# telecommandeV.net
KiCad netlist of a schematic drawn in EAGLE
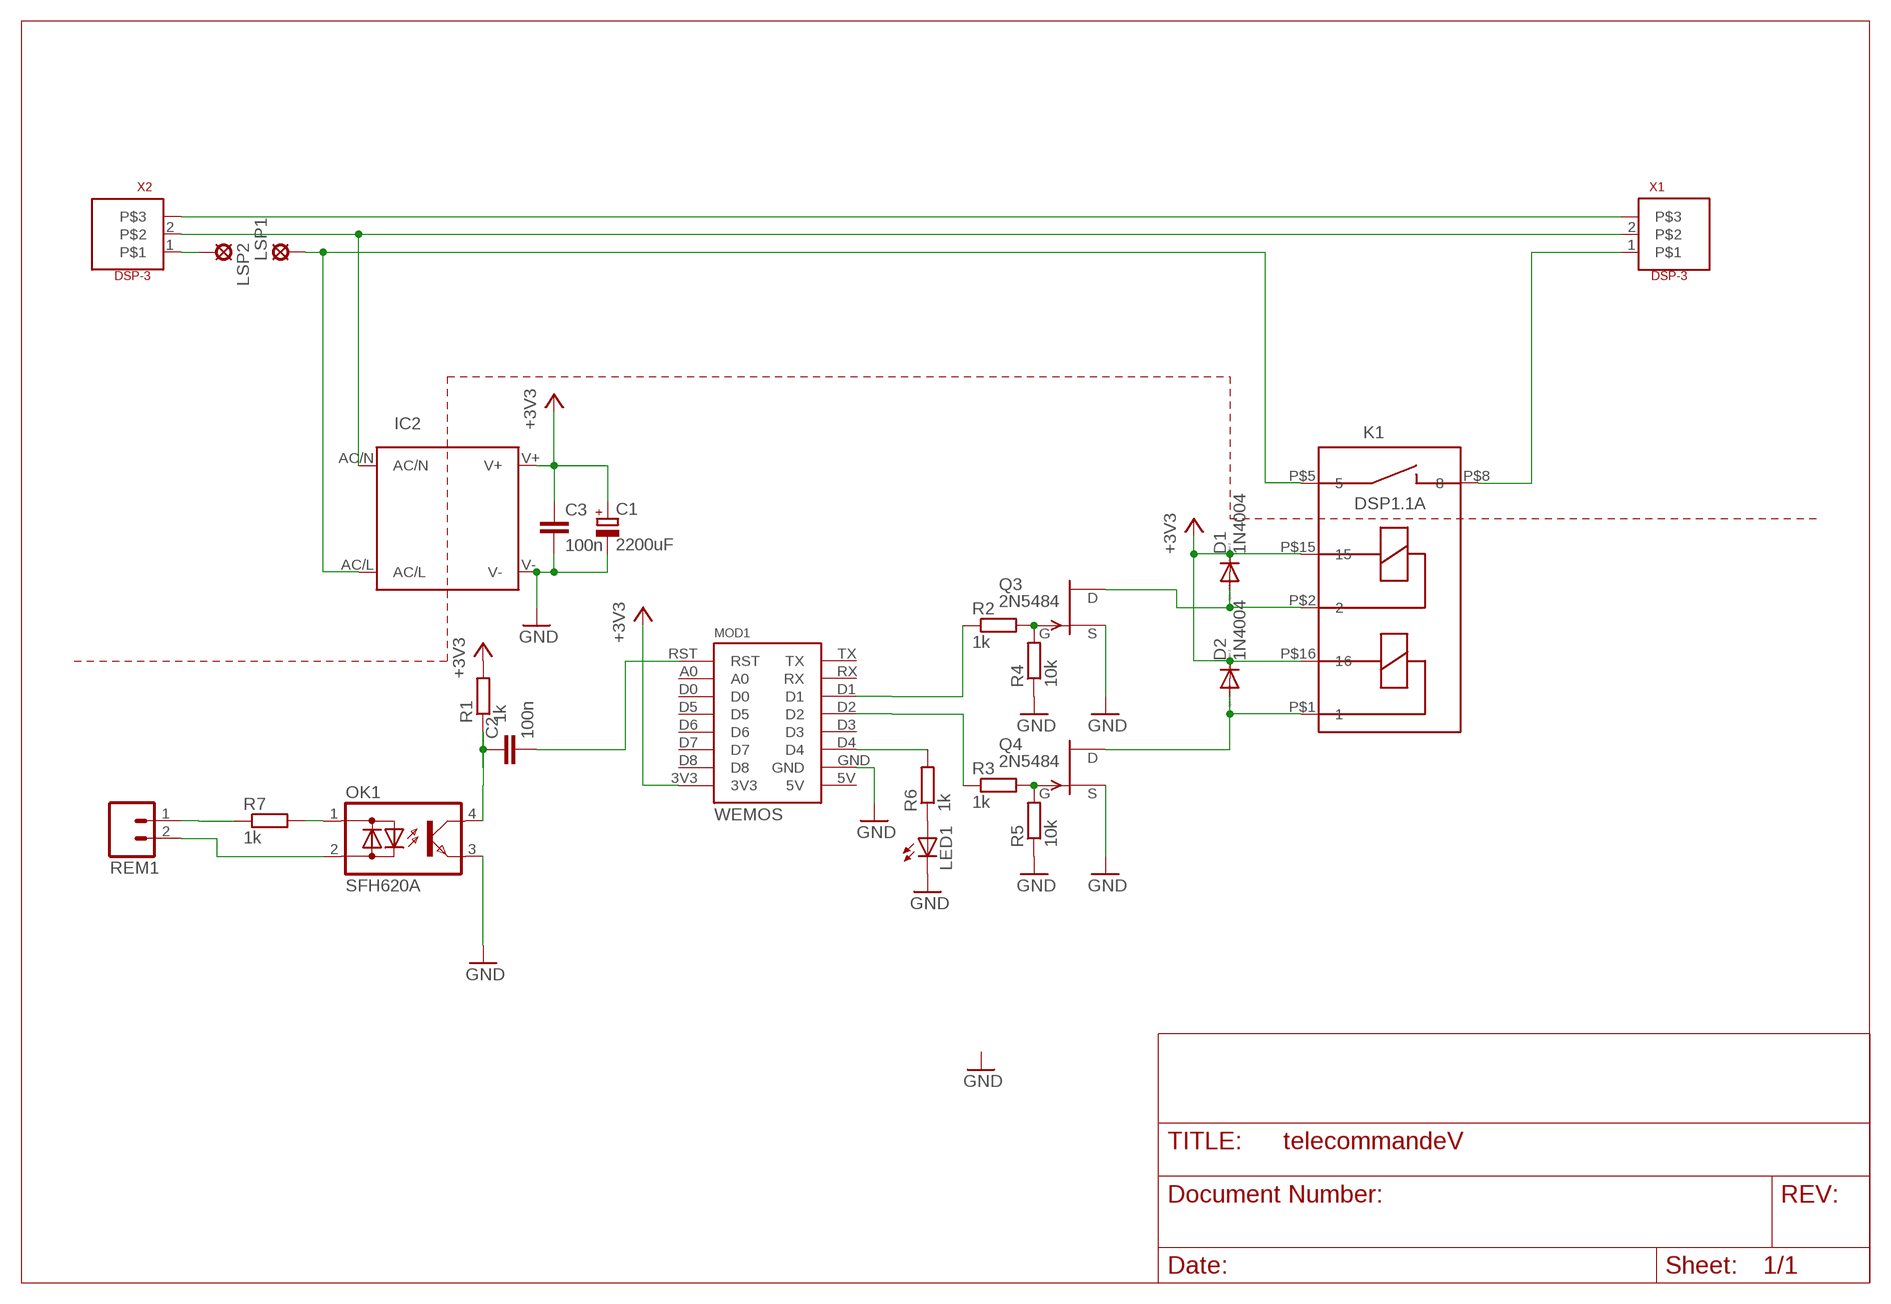
[diagram p0: schematic, sheet 1]

(export (version "E")
  (design (tool "Eeschema 10.0.6"))
  (components
    (comp (ref "C1")
      (value "2200uF")
      (footprint "eagle-import:E3,5-10")
      (libsource (lib "eagle-import") (part "CPOL-EUE3.5-10"))
    )
    (comp (ref "C2")
      (value "100n")
      (footprint "eagle-import:C025-024X044")
      (libsource (lib "eagle-import") (part "C-EU025-024X044"))
    )
    (comp (ref "C3")
      (value "100n")
      (footprint "eagle-import:C025-024X044")
      (libsource (lib "eagle-import") (part "C-EU025-024X044"))
    )
    (comp (ref "D1")
      (value "1N4004")
      (footprint "eagle-import:DO41-10")
      (libsource (lib "eagle-import") (part "1N4004"))
    )
    (comp (ref "D2")
      (value "1N4004")
      (footprint "eagle-import:DO41-10")
      (libsource (lib "eagle-import") (part "1N4004"))
    )
    (comp (ref "IC2")
      (value "IRM_03")
      (footprint "eagle-import:IRM_03")
      (libsource (lib "eagle-import") (part "IRM_03"))
    )
    (comp (ref "K1")
      (value "DSP1.1A")
      (footprint "eagle-import:DSP1A")
      (libsource (lib "eagle-import") (part "DSP1.1A"))
    )
    (comp (ref "LED1")
      (value "LED3MM")
      (footprint "eagle-import:LED3MM")
      (libsource (lib "eagle-import") (part "LED3MM"))
    )
    (comp (ref "LSP1")
      (value "SE14")
      (footprint "eagle-import:SE14")
      (libsource (lib "eagle-import") (part "SE14"))
    )
    (comp (ref "LSP2")
      (value "SE14")
      (footprint "eagle-import:SE14")
      (libsource (lib "eagle-import") (part "SE14"))
    )
    (comp (ref "MOD1")
      (value "WEMOS")
      (footprint "eagle-import:WEMOS")
      (libsource (lib "eagle-import") (part "WEMOS"))
    )
    (comp (ref "OK1")
      (value "SFH620A")
      (footprint "eagle-import:DIL04")
      (fields (field (name "MPN") "SFH620A-2"))
      (libsource (lib "eagle-import") (part "SFH620A"))
    )
    (comp (ref "Q3")
      (value "2N5484")
      (footprint "eagle-import:TO92-")
      (libsource (lib "eagle-import") (part "?5482N4"))
    )
    (comp (ref "Q4")
      (value "2N5484")
      (footprint "eagle-import:TO92-")
      (libsource (lib "eagle-import") (part "?5482N4"))
    )
    (comp (ref "R1")
      (value "1k")
      (footprint "eagle-import:0204_7")
      (libsource (lib "eagle-import") (part "R-EU_0204/7"))
    )
    (comp (ref "R2")
      (value "1k")
      (footprint "eagle-import:0204_7")
      (libsource (lib "eagle-import") (part "R-EU_0204/7"))
    )
    (comp (ref "R3")
      (value "1k")
      (footprint "eagle-import:0204_7")
      (libsource (lib "eagle-import") (part "R-EU_0204/7"))
    )
    (comp (ref "R4")
      (value "10k")
      (footprint "eagle-import:0204_7")
      (libsource (lib "eagle-import") (part "R-EU_0204/7"))
    )
    (comp (ref "R5")
      (value "10k")
      (footprint "eagle-import:0204_7")
      (libsource (lib "eagle-import") (part "R-EU_0204/7"))
    )
    (comp (ref "R6")
      (value "1k")
      (footprint "eagle-import:0204_7")
      (libsource (lib "eagle-import") (part "R-EU_0204/7"))
    )
    (comp (ref "R7")
      (value "1k")
      (footprint "eagle-import:0207_10")
      (libsource (lib "eagle-import") (part "R-EU_0207/10"))
    )
    (comp (ref "REM1")
      (value "M025MM")
      (footprint "eagle-import:SCREWTERMINAL-5MM-2")
      (libsource (lib "eagle-import") (part "M025MM"))
    )
    (comp (ref "X1")
      (value "DSP-3")
      (footprint "eagle-import:RND-CONNECT-3")
      (libsource (lib "eagle-import") (part "DSP-3"))
    )
    (comp (ref "X2")
      (value "DSP-3")
      (footprint "eagle-import:RND-CONNECT-3")
      (libsource (lib "eagle-import") (part "DSP-3"))
    )
  )
  (nets
    (net (code "1") (name "+3V3") (class "Default")
      (node (ref "C1") (pin "+") (pinfunction "+_+") (pintype "passive"))
      (node (ref "C3") (pin "1") (pinfunction "1_1") (pintype "passive"))
      (node (ref "D1") (pin "C") (pinfunction "C_C") (pintype "passive"))
      (node (ref "D2") (pin "C") (pinfunction "C_C") (pintype "passive"))
      (node (ref "IC2") (pin "V+") (pinfunction "V+_V+") (pintype "output"))
      (node (ref "K1") (pin "P$15") (pinfunction "15_P$15") (pintype "bidirectional"))
      (node (ref "K1") (pin "P$16") (pinfunction "16_P$16") (pintype "bidirectional"))
      (node (ref "MOD1") (pin "3V3") (pinfunction "3V3_3V3") (pintype "bidirectional"))
      (node (ref "R1") (pin "2") (pinfunction "2_2") (pintype "passive"))
    )
    (net (code "2") (name "GND") (class "Default")
      (node (ref "C1") (pin "-") (pinfunction "-_-") (pintype "passive"))
      (node (ref "C3") (pin "2") (pinfunction "2_2") (pintype "passive"))
      (node (ref "IC2") (pin "V-") (pinfunction "V-_V-") (pintype "output"))
      (node (ref "LED1") (pin "K") (pinfunction "C_K") (pintype "passive"))
      (node (ref "MOD1") (pin "GND") (pinfunction "GND_GND") (pintype "bidirectional"))
      (node (ref "OK1") (pin "3") (pinfunction "E_3") (pintype "passive"))
      (node (ref "Q3") (pin "2") (pinfunction "S_2") (pintype "passive"))
      (node (ref "Q4") (pin "2") (pinfunction "S_2") (pintype "passive"))
      (node (ref "R4") (pin "1") (pinfunction "1_1") (pintype "passive"))
      (node (ref "R5") (pin "1") (pinfunction "1_1") (pintype "passive"))
    )
    (net (code "3") (name "Net-(C2-Pad2)") (class "Default")
      (node (ref "C2") (pin "2") (pinfunction "2_2") (pintype "passive"))
      (node (ref "MOD1") (pin "RST") (pinfunction "RST_RST") (pintype "bidirectional"))
    )
    (net (code "4") (name "Net-(K1-1)") (class "Default")
      (node (ref "D2") (pin "A") (pinfunction "A_A") (pintype "passive"))
      (node (ref "K1") (pin "P$1") (pinfunction "1_P$1") (pintype "bidirectional"))
      (node (ref "Q4") (pin "3") (pinfunction "D_3") (pintype "passive"))
    )
    (net (code "5") (name "Net-(K1-2)") (class "Default")
      (node (ref "D1") (pin "A") (pinfunction "A_A") (pintype "passive"))
      (node (ref "K1") (pin "P$2") (pinfunction "2_P$2") (pintype "bidirectional"))
      (node (ref "Q3") (pin "3") (pinfunction "D_3") (pintype "passive"))
    )
    (net (code "6") (name "Net-(K1-5)") (class "Default")
      (node (ref "IC2") (pin "AC/L") (pinfunction "AC/L_AC/L") (pintype "input"))
      (node (ref "K1") (pin "P$5") (pinfunction "5_P$5") (pintype "bidirectional"))
      (node (ref "LSP1") (pin "MP") (pinfunction "MP_MP") (pintype "passive"))
    )
    (net (code "7") (name "Net-(K1-8)") (class "Default")
      (node (ref "K1") (pin "P$8") (pinfunction "8_P$8") (pintype "bidirectional"))
      (node (ref "X1") (pin "1") (pinfunction "P$1_1") (pintype "bidirectional"))
    )
    (net (code "8") (name "Net-(LED1-PadA)") (class "Default")
      (node (ref "LED1") (pin "A") (pinfunction "A_A") (pintype "passive"))
      (node (ref "R6") (pin "1") (pinfunction "1_1") (pintype "passive"))
    )
    (net (code "9") (name "Net-(MOD1-PadD1)") (class "Default")
      (node (ref "MOD1") (pin "D1") (pinfunction "D1_D1") (pintype "bidirectional"))
      (node (ref "R2") (pin "1") (pinfunction "1_1") (pintype "passive"))
    )
    (net (code "10") (name "Net-(MOD1-PadD2)") (class "Default")
      (node (ref "MOD1") (pin "D2") (pinfunction "D2_D2") (pintype "bidirectional"))
      (node (ref "R3") (pin "1") (pinfunction "1_1") (pintype "passive"))
    )
    (net (code "11") (name "Net-(MOD1-PadD4)") (class "Default")
      (node (ref "MOD1") (pin "D4") (pinfunction "D4_D4") (pintype "bidirectional"))
      (node (ref "R6") (pin "2") (pinfunction "2_2") (pintype "passive"))
    )
    (net (code "12") (name "Net-(OK1-AC1)") (class "Default")
      (node (ref "OK1") (pin "1") (pinfunction "AC1_1") (pintype "passive"))
      (node (ref "R7") (pin "2") (pinfunction "2_2") (pintype "passive"))
    )
    (net (code "13") (name "Net-(OK1-AC2)") (class "Default")
      (node (ref "OK1") (pin "2") (pinfunction "AC2_2") (pintype "passive"))
      (node (ref "REM1") (pin "2") (pinfunction "2_2") (pintype "passive"))
    )
    (net (code "14") (name "Net-(OK1-C)") (class "Default")
      (node (ref "C2") (pin "1") (pinfunction "1_1") (pintype "passive"))
      (node (ref "OK1") (pin "4") (pinfunction "C_4") (pintype "passive"))
      (node (ref "R1") (pin "1") (pinfunction "1_1") (pintype "passive"))
    )
    (net (code "15") (name "Net-(Q3-G)") (class "Default")
      (node (ref "Q3") (pin "1") (pinfunction "G_1") (pintype "passive"))
      (node (ref "R2") (pin "2") (pinfunction "2_2") (pintype "passive"))
      (node (ref "R4") (pin "2") (pinfunction "2_2") (pintype "passive"))
    )
    (net (code "16") (name "Net-(Q4-G)") (class "Default")
      (node (ref "Q4") (pin "1") (pinfunction "G_1") (pintype "passive"))
      (node (ref "R3") (pin "2") (pinfunction "2_2") (pintype "passive"))
      (node (ref "R5") (pin "2") (pinfunction "2_2") (pintype "passive"))
    )
    (net (code "17") (name "Net-(R7-Pad1)") (class "Default")
      (node (ref "R7") (pin "1") (pinfunction "1_1") (pintype "passive"))
      (node (ref "REM1") (pin "1") (pinfunction "1_1") (pintype "passive"))
    )
    (net (code "18") (name "Net-(X1-P$2)") (class "Default")
      (node (ref "IC2") (pin "AC/N") (pinfunction "AC/N_AC/N") (pintype "input"))
      (node (ref "X1") (pin "2") (pinfunction "P$2_2") (pintype "bidirectional"))
      (node (ref "X2") (pin "2") (pinfunction "P$2_2") (pintype "bidirectional"))
    )
    (net (code "19") (name "Net-(X1-P$3)") (class "Default")
      (node (ref "X1") (pin "3") (pinfunction "P$3_3") (pintype "bidirectional"))
      (node (ref "X2") (pin "3") (pinfunction "P$3_3") (pintype "bidirectional"))
    )
    (net (code "20") (name "Net-(X2-P$1)") (class "Default")
      (node (ref "LSP2") (pin "MP") (pinfunction "MP_MP") (pintype "passive"))
      (node (ref "X2") (pin "1") (pinfunction "P$1_1") (pintype "bidirectional"))
    )
    (net (code "21") (name "unconnected-(MOD1-Pad5V)") (class "Default")
      (node (ref "MOD1") (pin "5V") (pinfunction "5V_5V") (pintype "bidirectional"))
    )
    (net (code "22") (name "unconnected-(MOD1-PadA0)") (class "Default")
      (node (ref "MOD1") (pin "A0") (pinfunction "A0_A0") (pintype "bidirectional"))
    )
    (net (code "23") (name "unconnected-(MOD1-PadD0)") (class "Default")
      (node (ref "MOD1") (pin "D0") (pinfunction "D0_D0") (pintype "bidirectional"))
    )
    (net (code "24") (name "unconnected-(MOD1-PadD3)") (class "Default")
      (node (ref "MOD1") (pin "D3") (pinfunction "D3_D3") (pintype "bidirectional"))
    )
    (net (code "25") (name "unconnected-(MOD1-PadD5)") (class "Default")
      (node (ref "MOD1") (pin "D5") (pinfunction "D5_D5") (pintype "bidirectional"))
    )
    (net (code "26") (name "unconnected-(MOD1-PadD6)") (class "Default")
      (node (ref "MOD1") (pin "D6") (pinfunction "D6_D6") (pintype "bidirectional"))
    )
    (net (code "27") (name "unconnected-(MOD1-PadD7)") (class "Default")
      (node (ref "MOD1") (pin "D7") (pinfunction "D7_D7") (pintype "bidirectional"))
    )
    (net (code "28") (name "unconnected-(MOD1-PadD8)") (class "Default")
      (node (ref "MOD1") (pin "D8") (pinfunction "D8_D8") (pintype "bidirectional"))
    )
    (net (code "29") (name "unconnected-(MOD1-PadRX)") (class "Default")
      (node (ref "MOD1") (pin "RX") (pinfunction "RX_RX") (pintype "bidirectional"))
    )
    (net (code "30") (name "unconnected-(MOD1-PadTX)") (class "Default")
      (node (ref "MOD1") (pin "TX") (pinfunction "TX_TX") (pintype "bidirectional"))
    )
  )
)
